# led_driver.net
KiCad netlist of a schematic drawn in EAGLE
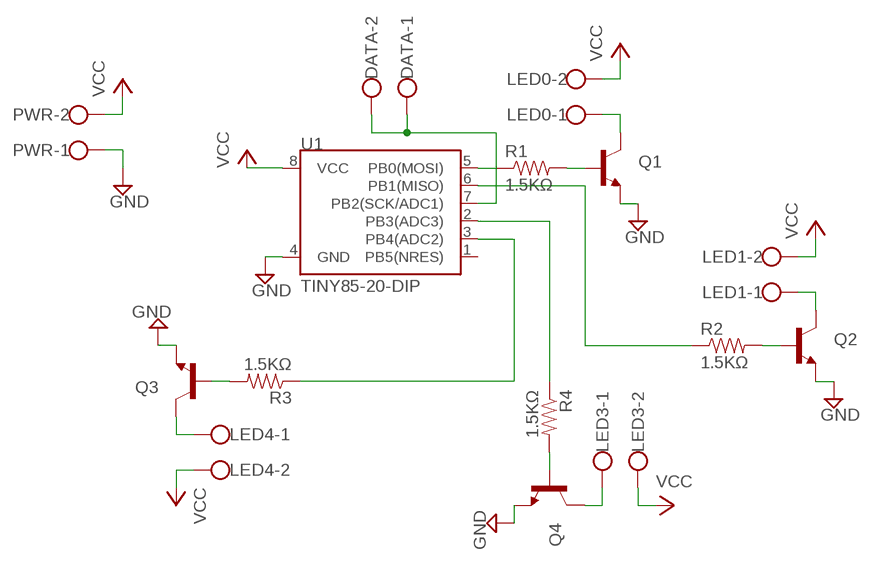
[diagram p0: schematic, sheet 1]

(export (version "E")
  (design (tool "Eeschema 10.0.6"))
  (components
    (comp (ref "DATA")
      (value "W237-102")
      (footprint "eagle-import:W237-102")
      (fields (field (name "MPN") "237-102"))
      (libsource (lib "eagle-import") (part "W237-102"))
    )
    (comp (ref "LED0")
      (value "W237-102")
      (footprint "eagle-import:W237-102")
      (fields (field (name "MPN") "237-102"))
      (libsource (lib "eagle-import") (part "W237-102"))
    )
    (comp (ref "LED1")
      (value "W237-102")
      (footprint "eagle-import:W237-102")
      (fields (field (name "MPN") "237-102"))
      (libsource (lib "eagle-import") (part "W237-102"))
    )
    (comp (ref "LED3")
      (value "W237-102")
      (footprint "eagle-import:W237-102")
      (fields (field (name "MPN") "237-102"))
      (libsource (lib "eagle-import") (part "W237-102"))
    )
    (comp (ref "LED4")
      (value "W237-102")
      (footprint "eagle-import:W237-102")
      (fields (field (name "MPN") "237-102"))
      (libsource (lib "eagle-import") (part "W237-102"))
    )
    (comp (ref "PWR")
      (value "W237-102")
      (footprint "eagle-import:W237-102")
      (fields (field (name "MPN") "237-102"))
      (libsource (lib "eagle-import") (part "W237-102"))
    )
    (comp (ref "Q1")
      (value "TRANSISTOR_NPNBC547")
      (footprint "eagle-import:TO-92-AMMO")
      (libsource (lib "eagle-import") (part "TRANSISTOR_NPNBC547"))
    )
    (comp (ref "Q2")
      (value "TRANSISTOR_NPNBC547")
      (footprint "eagle-import:TO-92-AMMO")
      (libsource (lib "eagle-import") (part "TRANSISTOR_NPNBC547"))
    )
    (comp (ref "Q3")
      (value "TRANSISTOR_NPNBC547")
      (footprint "eagle-import:TO-92-AMMO")
      (libsource (lib "eagle-import") (part "TRANSISTOR_NPNBC547"))
    )
    (comp (ref "Q4")
      (value "TRANSISTOR_NPNBC547")
      (footprint "eagle-import:TO-92-AMMO")
      (libsource (lib "eagle-import") (part "TRANSISTOR_NPNBC547"))
    )
    (comp (ref "R1")
      (value "1.5ΚΩ")
      (footprint "eagle-import:AXIAL-0.3")
      (libsource (lib "eagle-import") (part "RESISTORAXIAL-0.3"))
    )
    (comp (ref "R2")
      (value "1.5ΚΩ")
      (footprint "eagle-import:AXIAL-0.3")
      (libsource (lib "eagle-import") (part "RESISTORAXIAL-0.3"))
    )
    (comp (ref "R3")
      (value "1.5KΩ")
      (footprint "eagle-import:AXIAL-0.3")
      (libsource (lib "eagle-import") (part "RESISTORAXIAL-0.3"))
    )
    (comp (ref "R4")
      (value "1.5ΚΩ")
      (footprint "eagle-import:AXIAL-0.3")
      (libsource (lib "eagle-import") (part "RESISTORAXIAL-0.3"))
    )
    (comp (ref "U1")
      (value "TINY85-20-DIP")
      (footprint "eagle-import:DIP08")
      (libsource (lib "eagle-import") (part "ATTINY45TINY85-20-DIP"))
    )
  )
  (nets
    (net (code "1") (name "GND") (class "Default")
      (node (ref "PWR") (pin "1") (pinfunction "KL_1") (pintype "passive"))
      (node (ref "Q1") (pin "3") (pinfunction "E_3") (pintype "passive"))
      (node (ref "Q2") (pin "3") (pinfunction "E_3") (pintype "passive"))
      (node (ref "Q3") (pin "3") (pinfunction "E_3") (pintype "passive"))
      (node (ref "Q4") (pin "3") (pinfunction "E_3") (pintype "passive"))
      (node (ref "U1") (pin "4") (pinfunction "GND_4") (pintype "bidirectional"))
    )
    (net (code "2") (name "Net-(DATAA-KL)") (class "Default")
      (node (ref "DATA") (pin "1") (pinfunction "KL_1") (pintype "passive"))
      (node (ref "DATA") (pin "2") (pinfunction "KL_2") (pintype "passive"))
      (node (ref "U1") (pin "7") (pinfunction "PB2(SCK/ADC1)_7") (pintype "bidirectional"))
    )
    (net (code "3") (name "Net-(LED0A-KL)") (class "Default")
      (node (ref "LED0") (pin "1") (pinfunction "KL_1") (pintype "passive"))
      (node (ref "Q1") (pin "1") (pinfunction "C_1") (pintype "passive"))
    )
    (net (code "4") (name "Net-(LED1A-KL)") (class "Default")
      (node (ref "LED1") (pin "1") (pinfunction "KL_1") (pintype "passive"))
      (node (ref "Q2") (pin "1") (pinfunction "C_1") (pintype "passive"))
    )
    (net (code "5") (name "Net-(LED3A-KL)") (class "Default")
      (node (ref "LED3") (pin "1") (pinfunction "KL_1") (pintype "passive"))
      (node (ref "Q4") (pin "1") (pinfunction "C_1") (pintype "passive"))
    )
    (net (code "6") (name "Net-(LED4A-KL)") (class "Default")
      (node (ref "LED4") (pin "1") (pinfunction "KL_1") (pintype "passive"))
      (node (ref "Q3") (pin "1") (pinfunction "C_1") (pintype "passive"))
    )
    (net (code "7") (name "Net-(Q1-B)") (class "Default")
      (node (ref "Q1") (pin "2") (pinfunction "B_2") (pintype "passive"))
      (node (ref "R1") (pin "P$2") (pinfunction "2_P$2") (pintype "passive"))
    )
    (net (code "8") (name "Net-(Q2-B)") (class "Default")
      (node (ref "Q2") (pin "2") (pinfunction "B_2") (pintype "passive"))
      (node (ref "R2") (pin "P$2") (pinfunction "2_P$2") (pintype "passive"))
    )
    (net (code "9") (name "Net-(Q3-B)") (class "Default")
      (node (ref "Q3") (pin "2") (pinfunction "B_2") (pintype "passive"))
      (node (ref "R3") (pin "P$2") (pinfunction "2_P$2") (pintype "passive"))
    )
    (net (code "10") (name "Net-(Q4-B)") (class "Default")
      (node (ref "Q4") (pin "2") (pinfunction "B_2") (pintype "passive"))
      (node (ref "R4") (pin "P$2") (pinfunction "2_P$2") (pintype "passive"))
    )
    (net (code "11") (name "Net-(R1-1)") (class "Default")
      (node (ref "R1") (pin "P$1") (pinfunction "1_P$1") (pintype "passive"))
      (node (ref "U1") (pin "5") (pinfunction "PB0(MOSI)_5") (pintype "bidirectional"))
    )
    (net (code "12") (name "Net-(R2-1)") (class "Default")
      (node (ref "R2") (pin "P$1") (pinfunction "1_P$1") (pintype "passive"))
      (node (ref "U1") (pin "6") (pinfunction "PB1(MISO)_6") (pintype "bidirectional"))
    )
    (net (code "13") (name "Net-(R3-1)") (class "Default")
      (node (ref "R3") (pin "P$1") (pinfunction "1_P$1") (pintype "passive"))
      (node (ref "U1") (pin "3") (pinfunction "PB4(ADC2)_3") (pintype "bidirectional"))
    )
    (net (code "14") (name "Net-(R4-1)") (class "Default")
      (node (ref "R4") (pin "P$1") (pinfunction "1_P$1") (pintype "passive"))
      (node (ref "U1") (pin "2") (pinfunction "PB3(ADC3)_2") (pintype "bidirectional"))
    )
    (net (code "15") (name "VCC") (class "Default")
      (node (ref "LED0") (pin "2") (pinfunction "KL_2") (pintype "passive"))
      (node (ref "LED1") (pin "2") (pinfunction "KL_2") (pintype "passive"))
      (node (ref "LED3") (pin "2") (pinfunction "KL_2") (pintype "passive"))
      (node (ref "LED4") (pin "2") (pinfunction "KL_2") (pintype "passive"))
      (node (ref "PWR") (pin "2") (pinfunction "KL_2") (pintype "passive"))
      (node (ref "U1") (pin "8") (pinfunction "VCC_8") (pintype "bidirectional"))
    )
    (net (code "16") (name "unconnected-(U1-PB5(NRES)-Pad1)") (class "Default")
      (node (ref "U1") (pin "1") (pinfunction "PB5(NRES)_1") (pintype "bidirectional"))
    )
  )
)
